# Motherboard_simple.net
KiCad netlist of a schematic drawn in EAGLE
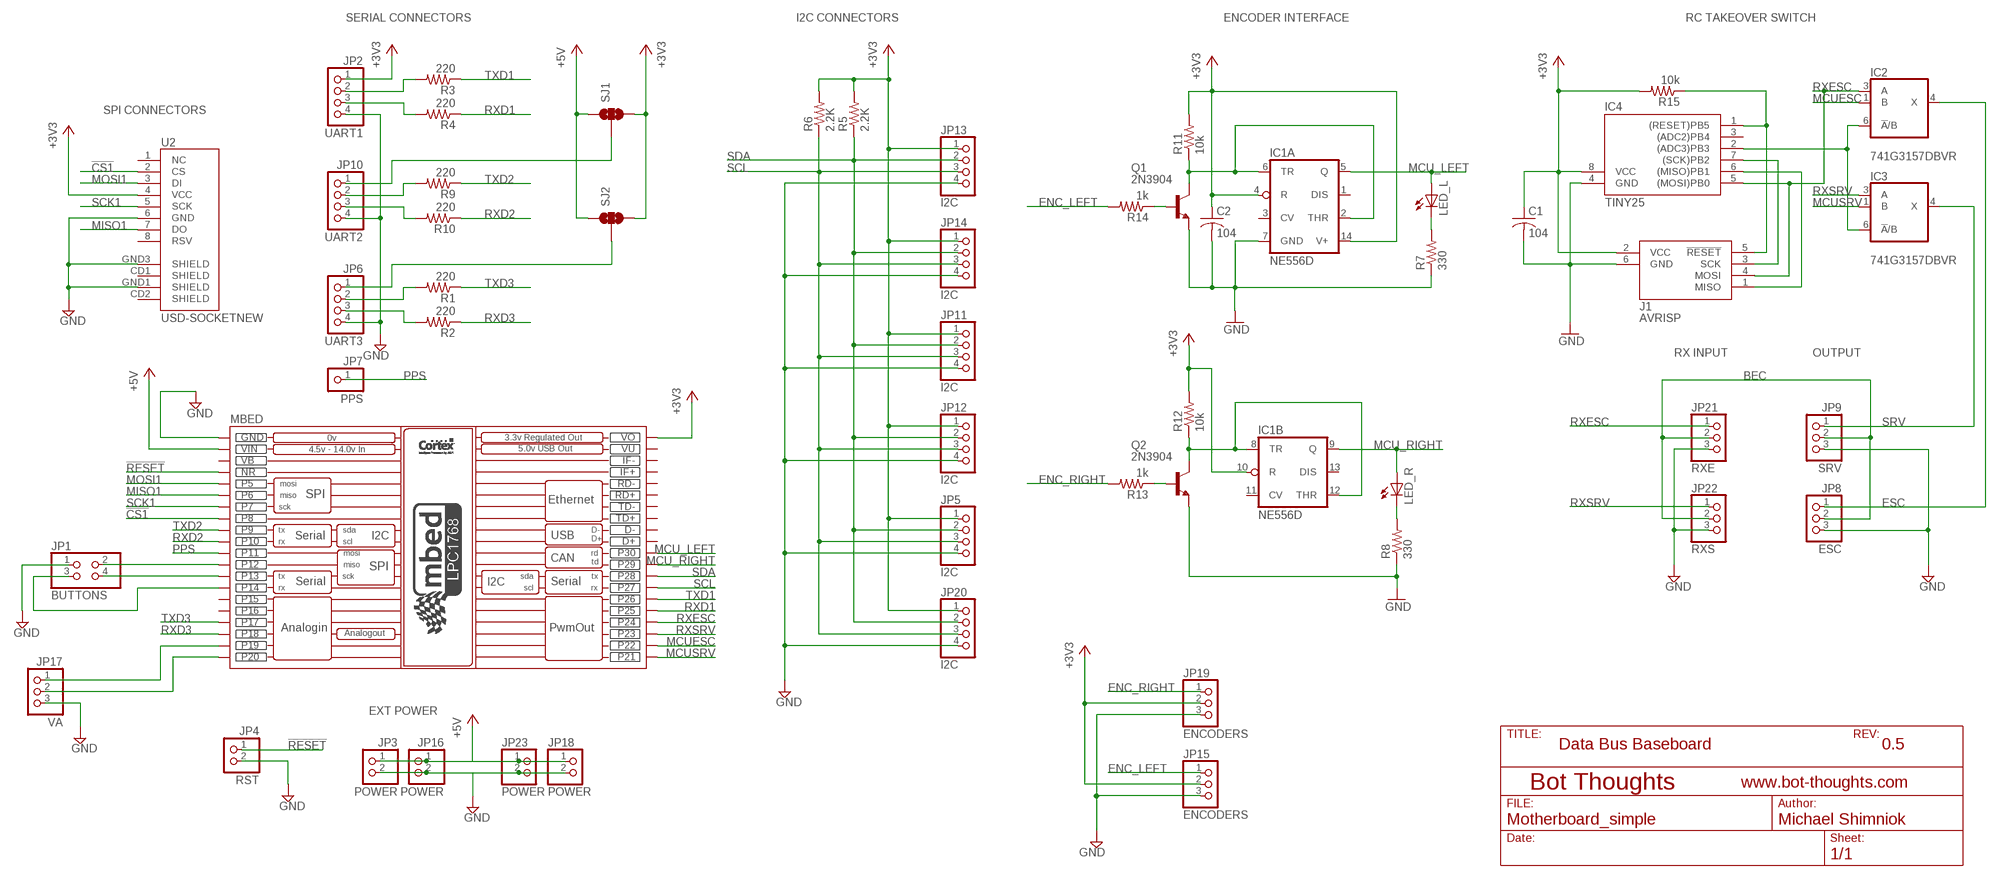
[diagram p0: schematic, sheet 1]

(export (version "E")
  (design (tool "Eeschema 10.0.6"))
  (components
    (comp (ref "C1")
      (value "104")
      (footprint "eagle-import:C050-025X075")
      (libsource (lib "eagle-import") (part "C-US050-025X075"))
    )
    (comp (ref "C2")
      (value "104")
      (footprint "eagle-import:C050-025X075")
      (libsource (lib "eagle-import") (part "C-US050-025X075"))
    )
    (comp (ref "IC1")
      (value "NE556D")
      (footprint "eagle-import:SO14")
      (libsource (lib "eagle-import") (part "556DNE"))
    )
    (comp (ref "IC2")
      (value "741G3157DBVR")
      (footprint "eagle-import:DBV_R-PDSO-G6")
      (libsource (lib "eagle-import") (part "741G3157DBVR"))
    )
    (comp (ref "IC3")
      (value "741G3157DBVR")
      (footprint "eagle-import:DBV_R-PDSO-G6")
      (libsource (lib "eagle-import") (part "741G3157DBVR"))
    )
    (comp (ref "IC4")
      (value "TINY25")
      (footprint "eagle-import:DIL08")
      (libsource (lib "eagle-import") (part "TINY138P3"))
    )
    (comp (ref "J1")
      (value "AVRISP")
      (footprint "eagle-import:CON6P2R")
      (libsource (lib "eagle-import") (part "AVRISP6"))
    )
    (comp (ref "JP1")
      (value "BUTTONS")
      (footprint "eagle-import:2X02")
      (libsource (lib "eagle-import") (part "PINHD-2X02_2.54"))
    )
    (comp (ref "JP2")
      (value "UART1")
      (footprint "eagle-import:1X04-S")
      (libsource (lib "eagle-import") (part "PINHD-1X04_2.54-S"))
    )
    (comp (ref "JP3")
      (value "POWER")
      (footprint "eagle-import:1X02-S")
      (libsource (lib "eagle-import") (part "PINHD-1X02_2.54-S"))
    )
    (comp (ref "JP4")
      (value "RST")
      (footprint "eagle-import:1X02-S")
      (libsource (lib "eagle-import") (part "PINHD-1X02_2.54-S"))
    )
    (comp (ref "JP5")
      (value "I2C")
      (footprint "eagle-import:1X04-S")
      (libsource (lib "eagle-import") (part "PINHD-1X04_2.54-S"))
    )
    (comp (ref "JP6")
      (value "UART3")
      (footprint "eagle-import:1X04-S")
      (libsource (lib "eagle-import") (part "PINHD-1X04_2.54-S"))
    )
    (comp (ref "JP7")
      (value "PPS")
      (footprint "eagle-import:1X01-S")
      (libsource (lib "eagle-import") (part "PINHD-1X01_2.54-S"))
    )
    (comp (ref "JP8")
      (value "ESC")
      (footprint "eagle-import:1X03-S")
      (libsource (lib "eagle-import") (part "PINHD-1X03_2.54-S"))
    )
    (comp (ref "JP9")
      (value "SRV")
      (footprint "eagle-import:1X03-S")
      (libsource (lib "eagle-import") (part "PINHD-1X03_2.54-S"))
    )
    (comp (ref "JP10")
      (value "UART2")
      (footprint "eagle-import:1X04-S")
      (libsource (lib "eagle-import") (part "PINHD-1X04_2.54-S"))
    )
    (comp (ref "JP11")
      (value "I2C")
      (footprint "eagle-import:1X04-S")
      (libsource (lib "eagle-import") (part "PINHD-1X04_2.54-S"))
    )
    (comp (ref "JP12")
      (value "I2C")
      (footprint "eagle-import:1X04-S")
      (libsource (lib "eagle-import") (part "PINHD-1X04_2.54-S"))
    )
    (comp (ref "JP13")
      (value "I2C")
      (footprint "eagle-import:1X04-S")
      (libsource (lib "eagle-import") (part "PINHD-1X04_2.54-S"))
    )
    (comp (ref "JP14")
      (value "I2C")
      (footprint "eagle-import:1X04-S")
      (libsource (lib "eagle-import") (part "PINHD-1X04_2.54-S"))
    )
    (comp (ref "JP15")
      (value "ENCODERS")
      (footprint "eagle-import:1X03-S")
      (libsource (lib "eagle-import") (part "PINHD-1X03_2.54-S"))
    )
    (comp (ref "JP16")
      (value "POWER")
      (footprint "eagle-import:1X02-S")
      (libsource (lib "eagle-import") (part "PINHD-1X02_2.54-S"))
    )
    (comp (ref "JP17")
      (value "VA")
      (footprint "eagle-import:1X03-S")
      (libsource (lib "eagle-import") (part "PINHD-1X03_2.54-S"))
    )
    (comp (ref "JP18")
      (value "POWER")
      (footprint "eagle-import:1X02-S")
      (libsource (lib "eagle-import") (part "PINHD-1X02_2.54-S"))
    )
    (comp (ref "JP19")
      (value "ENCODERS")
      (footprint "eagle-import:1X03-S")
      (libsource (lib "eagle-import") (part "PINHD-1X03_2.54-S"))
    )
    (comp (ref "JP20")
      (value "I2C")
      (footprint "eagle-import:1X04-S")
      (libsource (lib "eagle-import") (part "PINHD-1X04_2.54-S"))
    )
    (comp (ref "JP21")
      (value "RXE")
      (footprint "eagle-import:1X03-S")
      (libsource (lib "eagle-import") (part "PINHD-1X03_2.54-S"))
    )
    (comp (ref "JP22")
      (value "RXS")
      (footprint "eagle-import:1X03-S")
      (libsource (lib "eagle-import") (part "PINHD-1X03_2.54-S"))
    )
    (comp (ref "JP23")
      (value "POWER")
      (footprint "eagle-import:1X02-S")
      (libsource (lib "eagle-import") (part "PINHD-1X02_2.54-S"))
    )
    (comp (ref "LED_L")
      (value "LED3MM")
      (footprint "eagle-import:LED3MM")
      (libsource (lib "eagle-import") (part "LED3MM"))
    )
    (comp (ref "LED_R")
      (value "LED3MM")
      (footprint "eagle-import:LED3MM")
      (libsource (lib "eagle-import") (part "LED3MM"))
    )
    (comp (ref "MBED")
      (value "MBED_NXP_LPC1768")
      (footprint "eagle-import:MBED-KIT")
      (fields (field (name "MPN") "2212S-20SG-85"))
      (libsource (lib "eagle-import") (part "MBED_NXP_LPC1768"))
    )
    (comp (ref "Q1")
      (value "2N3904")
      (footprint "eagle-import:TO92")
      (libsource (lib "eagle-import") (part "2N3904"))
    )
    (comp (ref "Q2")
      (value "2N3904")
      (footprint "eagle-import:TO92")
      (libsource (lib "eagle-import") (part "2N3904"))
    )
    (comp (ref "R1")
      (value "220")
      (footprint "eagle-import:0204_5")
      (fields (field (name "MPN") "WCR0805-220RFI"))
      (libsource (lib "eagle-import") (part "R-US_0204/5"))
    )
    (comp (ref "R2")
      (value "220")
      (footprint "eagle-import:0204_5")
      (fields (field (name "MPN") "WCR0805-220RFI"))
      (libsource (lib "eagle-import") (part "R-US_0204/5"))
    )
    (comp (ref "R3")
      (value "220")
      (footprint "eagle-import:0204_5")
      (fields (field (name "MPN") "WCR0805-220RFI"))
      (libsource (lib "eagle-import") (part "R-US_0204/5"))
    )
    (comp (ref "R4")
      (value "220")
      (footprint "eagle-import:0204_5")
      (fields (field (name "MPN") "WCR0805-220RFI"))
      (libsource (lib "eagle-import") (part "R-US_0204/5"))
    )
    (comp (ref "R5")
      (value "2.2K")
      (footprint "eagle-import:0204_5")
      (libsource (lib "eagle-import") (part "R-US_0204/5"))
    )
    (comp (ref "R6")
      (value "2.2K")
      (footprint "eagle-import:0204_5")
      (libsource (lib "eagle-import") (part "R-US_0204/5"))
    )
    (comp (ref "R7")
      (value "330")
      (footprint "eagle-import:0204_5")
      (libsource (lib "eagle-import") (part "R-US_0204/5"))
    )
    (comp (ref "R8")
      (value "330")
      (footprint "eagle-import:0204_5")
      (libsource (lib "eagle-import") (part "R-US_0204/5"))
    )
    (comp (ref "R9")
      (value "220")
      (footprint "eagle-import:0204_5")
      (fields (field (name "MPN") "WCR0805-220RFI"))
      (libsource (lib "eagle-import") (part "R-US_0204/5"))
    )
    (comp (ref "R10")
      (value "220")
      (footprint "eagle-import:0204_5")
      (fields (field (name "MPN") "WCR0805-220RFI"))
      (libsource (lib "eagle-import") (part "R-US_0204/5"))
    )
    (comp (ref "R11")
      (value "10k")
      (footprint "eagle-import:0204_5")
      (libsource (lib "eagle-import") (part "R-US_0204/5"))
    )
    (comp (ref "R12")
      (value "10k")
      (footprint "eagle-import:0204_5")
      (libsource (lib "eagle-import") (part "R-US_0204/5"))
    )
    (comp (ref "R13")
      (value "1k")
      (footprint "eagle-import:0204_5")
      (libsource (lib "eagle-import") (part "R-US_0204/5"))
    )
    (comp (ref "R14")
      (value "1k")
      (footprint "eagle-import:0204_5")
      (libsource (lib "eagle-import") (part "R-US_0204/5"))
    )
    (comp (ref "R15")
      (value "10k")
      (footprint "eagle-import:0204_5")
      (libsource (lib "eagle-import") (part "R-US_0204/5"))
    )
    (comp (ref "SJ1")
      (value "SOLDERJUMPER_2WAYS")
      (footprint "eagle-import:SJ_3")
      (libsource (lib "eagle-import") (part "SOLDERJUMPER_2WAYS"))
    )
    (comp (ref "SJ2")
      (value "SOLDERJUMPER_2WAYS")
      (footprint "eagle-import:SJ_3")
      (libsource (lib "eagle-import") (part "SOLDERJUMPER_2WAYS"))
    )
    (comp (ref "U2")
      (value "USD-SOCKETNEW")
      (footprint "eagle-import:MICRO-SD-SOCKET-PP")
      (libsource (lib "eagle-import") (part "USD-SOCKETNEW"))
    )
  )
  (nets
    (net (code "1") (name "+3V3") (class "Default")
      (node (ref "C1") (pin "1") (pinfunction "1_1") (pintype "passive"))
      (node (ref "C2") (pin "1") (pinfunction "1_1") (pintype "passive"))
      (node (ref "IC1") (pin "10") (pinfunction "R_10") (pintype "input"))
      (node (ref "IC1") (pin "14") (pinfunction "V+_14") (pintype "power_in"))
      (node (ref "IC1") (pin "4") (pinfunction "R_4") (pintype "input"))
      (node (ref "IC4") (pin "8") (pinfunction "VCC_8") (pintype "power_in"))
      (node (ref "J1") (pin "2") (pinfunction "VCC_2") (pintype "power_in"))
      (node (ref "JP11") (pin "1") (pinfunction "1_1") (pintype "passive"))
      (node (ref "JP12") (pin "1") (pinfunction "1_1") (pintype "passive"))
      (node (ref "JP13") (pin "1") (pinfunction "1_1") (pintype "passive"))
      (node (ref "JP14") (pin "1") (pinfunction "1_1") (pintype "passive"))
      (node (ref "JP15") (pin "2") (pinfunction "2_2") (pintype "passive"))
      (node (ref "JP19") (pin "2") (pinfunction "2_2") (pintype "passive"))
      (node (ref "JP2") (pin "1") (pinfunction "1_1") (pintype "passive"))
      (node (ref "JP20") (pin "1") (pinfunction "1_1") (pintype "passive"))
      (node (ref "JP5") (pin "1") (pinfunction "1_1") (pintype "passive"))
      (node (ref "MBED") (pin "VOUT") (pinfunction "VO_VOUT") (pintype "power_in"))
      (node (ref "R11") (pin "2") (pinfunction "2_2") (pintype "passive"))
      (node (ref "R12") (pin "2") (pinfunction "2_2") (pintype "passive"))
      (node (ref "R15") (pin "2") (pinfunction "2_2") (pintype "passive"))
      (node (ref "R5") (pin "2") (pinfunction "2_2") (pintype "passive"))
      (node (ref "R6") (pin "2") (pinfunction "2_2") (pintype "passive"))
      (node (ref "SJ1") (pin "3") (pinfunction "3_3") (pintype "passive"))
      (node (ref "SJ2") (pin "3") (pinfunction "3_3") (pintype "passive"))
      (node (ref "U2") (pin "4") (pinfunction "VCC_4") (pintype "bidirectional"))
    )
    (net (code "2") (name "+5V") (class "Default")
      (node (ref "JP16") (pin "1") (pinfunction "1_1") (pintype "passive"))
      (node (ref "JP18") (pin "1") (pinfunction "1_1") (pintype "passive"))
      (node (ref "JP23") (pin "1") (pinfunction "1_1") (pintype "passive"))
      (node (ref "JP3") (pin "1") (pinfunction "1_1") (pintype "passive"))
      (node (ref "MBED") (pin "VIN") (pinfunction "VIN_VIN") (pintype "power_in"))
      (node (ref "SJ1") (pin "1") (pinfunction "1_1") (pintype "passive"))
      (node (ref "SJ2") (pin "1") (pinfunction "1_1") (pintype "passive"))
    )
    (net (code "3") (name "/BEC") (class "Default")
      (node (ref "JP21") (pin "2") (pinfunction "2_2") (pintype "passive"))
      (node (ref "JP22") (pin "2") (pinfunction "2_2") (pintype "passive"))
      (node (ref "JP8") (pin "2") (pinfunction "2_2") (pintype "passive"))
      (node (ref "JP9") (pin "2") (pinfunction "2_2") (pintype "passive"))
    )
    (net (code "4") (name "/ENC_LEFT") (class "Default")
      (node (ref "JP15") (pin "1") (pinfunction "1_1") (pintype "passive"))
      (node (ref "R14") (pin "2") (pinfunction "2_2") (pintype "passive"))
    )
    (net (code "5") (name "/ENC_RIGHT") (class "Default")
      (node (ref "JP19") (pin "1") (pinfunction "1_1") (pintype "passive"))
      (node (ref "R13") (pin "2") (pinfunction "2_2") (pintype "passive"))
    )
    (net (code "6") (name "/ESC") (class "Default")
      (node (ref "IC2") (pin "4") (pinfunction "X_4") (pintype "bidirectional"))
      (node (ref "JP8") (pin "1") (pinfunction "1_1") (pintype "passive"))
    )
    (net (code "7") (name "/MCUESC") (class "Default")
      (node (ref "IC2") (pin "1") (pinfunction "B_1") (pintype "bidirectional"))
      (node (ref "MBED") (pin "P$22") (pinfunction "P22_P$22") (pintype "bidirectional"))
    )
    (net (code "8") (name "/MCUSRV") (class "Default")
      (node (ref "IC3") (pin "1") (pinfunction "B_1") (pintype "bidirectional"))
      (node (ref "MBED") (pin "P$21") (pinfunction "P21_P$21") (pintype "bidirectional"))
    )
    (net (code "9") (name "/MCU_LEFT") (class "Default")
      (node (ref "IC1") (pin "5") (pinfunction "Q_5") (pintype "output"))
      (node (ref "LED_L") (pin "A") (pinfunction "A_A") (pintype "passive"))
      (node (ref "MBED") (pin "P$30") (pinfunction "P30_P$30") (pintype "bidirectional"))
    )
    (net (code "10") (name "/MCU_RIGHT") (class "Default")
      (node (ref "IC1") (pin "9") (pinfunction "Q_9") (pintype "output"))
      (node (ref "LED_R") (pin "A") (pinfunction "A_A") (pintype "passive"))
      (node (ref "MBED") (pin "P$29") (pinfunction "P29_P$29") (pintype "bidirectional"))
    )
    (net (code "11") (name "/MISO1") (class "Default")
      (node (ref "MBED") (pin "P$6") (pinfunction "P6_P$6") (pintype "bidirectional"))
      (node (ref "U2") (pin "7") (pinfunction "DO_7") (pintype "bidirectional"))
    )
    (net (code "12") (name "/MOSI1") (class "Default")
      (node (ref "MBED") (pin "P$5") (pinfunction "P5_P$5") (pintype "bidirectional"))
      (node (ref "U2") (pin "3") (pinfunction "DI_3") (pintype "bidirectional"))
    )
    (net (code "13") (name "/PPS") (class "Default")
      (node (ref "JP7") (pin "1") (pinfunction "1_1") (pintype "passive"))
      (node (ref "MBED") (pin "P$11") (pinfunction "P11_P$11") (pintype "bidirectional"))
    )
    (net (code "14") (name "/RXD1") (class "Default")
      (node (ref "MBED") (pin "P$25") (pinfunction "P25_P$25") (pintype "bidirectional"))
      (node (ref "R4") (pin "1") (pinfunction "1_1") (pintype "passive"))
    )
    (net (code "15") (name "/RXD2") (class "Default")
      (node (ref "MBED") (pin "P$10") (pinfunction "P10_P$10") (pintype "bidirectional"))
      (node (ref "R10") (pin "1") (pinfunction "1_1") (pintype "passive"))
    )
    (net (code "16") (name "/RXD3") (class "Default")
      (node (ref "MBED") (pin "P$18") (pinfunction "P18_P$18") (pintype "bidirectional"))
      (node (ref "R2") (pin "1") (pinfunction "1_1") (pintype "passive"))
    )
    (net (code "17") (name "/RXESC") (class "Default")
      (node (ref "IC2") (pin "3") (pinfunction "A_3") (pintype "bidirectional"))
      (node (ref "IC4") (pin "5") (pinfunction "(MOSI)PB0_5") (pintype "bidirectional"))
      (node (ref "J1") (pin "4") (pinfunction "MOSI_4") (pintype "output"))
      (node (ref "JP21") (pin "1") (pinfunction "1_1") (pintype "passive"))
      (node (ref "MBED") (pin "P$24") (pinfunction "P24_P$24") (pintype "bidirectional"))
    )
    (net (code "18") (name "/RXSRV") (class "Default")
      (node (ref "IC3") (pin "3") (pinfunction "A_3") (pintype "bidirectional"))
      (node (ref "JP22") (pin "1") (pinfunction "1_1") (pintype "passive"))
      (node (ref "MBED") (pin "P$23") (pinfunction "P23_P$23") (pintype "bidirectional"))
    )
    (net (code "19") (name "/SCK1") (class "Default")
      (node (ref "MBED") (pin "P$7") (pinfunction "P7_P$7") (pintype "bidirectional"))
      (node (ref "U2") (pin "5") (pinfunction "SCK_5") (pintype "bidirectional"))
    )
    (net (code "20") (name "/SCL") (class "Default")
      (node (ref "JP11") (pin "3") (pinfunction "3_3") (pintype "passive"))
      (node (ref "JP12") (pin "3") (pinfunction "3_3") (pintype "passive"))
      (node (ref "JP13") (pin "3") (pinfunction "3_3") (pintype "passive"))
      (node (ref "JP14") (pin "3") (pinfunction "3_3") (pintype "passive"))
      (node (ref "JP20") (pin "3") (pinfunction "3_3") (pintype "passive"))
      (node (ref "JP5") (pin "3") (pinfunction "3_3") (pintype "passive"))
      (node (ref "MBED") (pin "P$27") (pinfunction "P27_P$27") (pintype "bidirectional"))
      (node (ref "R6") (pin "1") (pinfunction "1_1") (pintype "passive"))
    )
    (net (code "21") (name "/SDA") (class "Default")
      (node (ref "JP11") (pin "2") (pinfunction "2_2") (pintype "passive"))
      (node (ref "JP12") (pin "2") (pinfunction "2_2") (pintype "passive"))
      (node (ref "JP13") (pin "2") (pinfunction "2_2") (pintype "passive"))
      (node (ref "JP14") (pin "2") (pinfunction "2_2") (pintype "passive"))
      (node (ref "JP20") (pin "2") (pinfunction "2_2") (pintype "passive"))
      (node (ref "JP5") (pin "2") (pinfunction "2_2") (pintype "passive"))
      (node (ref "MBED") (pin "P$28") (pinfunction "P28_P$28") (pintype "bidirectional"))
      (node (ref "R5") (pin "1") (pinfunction "1_1") (pintype "passive"))
    )
    (net (code "22") (name "/SRV") (class "Default")
      (node (ref "IC3") (pin "4") (pinfunction "X_4") (pintype "bidirectional"))
      (node (ref "JP9") (pin "1") (pinfunction "1_1") (pintype "passive"))
    )
    (net (code "23") (name "/TXD1") (class "Default")
      (node (ref "MBED") (pin "P$26") (pinfunction "P26_P$26") (pintype "bidirectional"))
      (node (ref "R3") (pin "1") (pinfunction "1_1") (pintype "passive"))
    )
    (net (code "24") (name "/TXD2") (class "Default")
      (node (ref "MBED") (pin "P$9") (pinfunction "P9_P$9") (pintype "bidirectional"))
      (node (ref "R9") (pin "1") (pinfunction "1_1") (pintype "passive"))
    )
    (net (code "25") (name "/TXD3") (class "Default")
      (node (ref "MBED") (pin "P$17") (pinfunction "P17_P$17") (pintype "bidirectional"))
      (node (ref "R1") (pin "1") (pinfunction "1_1") (pintype "passive"))
    )
    (net (code "26") (name "/VB") (class "Default")
      (node (ref "MBED") (pin "VB") (pinfunction "VB_VB") (pintype "power_in"))
    )
    (net (code "27") (name "/VU") (class "Default")
      (node (ref "MBED") (pin "VU") (pinfunction "VU_VU") (pintype "power_in"))
    )
    (net (code "28") (name "/~{CS1}") (class "Default")
      (node (ref "MBED") (pin "P$8") (pinfunction "P8_P$8") (pintype "bidirectional"))
      (node (ref "U2") (pin "2") (pinfunction "CS_2") (pintype "bidirectional"))
    )
    (net (code "29") (name "/~{RESET}") (class "Default")
      (node (ref "JP4") (pin "1") (pinfunction "1_1") (pintype "passive"))
      (node (ref "MBED") (pin "NR") (pinfunction "NR_NR") (pintype "power_in"))
    )
    (net (code "30") (name "GND") (class "Default")
      (node (ref "C1") (pin "2") (pinfunction "2_2") (pintype "passive"))
      (node (ref "C2") (pin "2") (pinfunction "2_2") (pintype "passive"))
      (node (ref "IC1") (pin "7") (pinfunction "GND_7") (pintype "power_in"))
      (node (ref "IC4") (pin "4") (pinfunction "GND_4") (pintype "power_in"))
      (node (ref "J1") (pin "6") (pinfunction "GND_6") (pintype "power_in"))
      (node (ref "JP1") (pin "1") (pinfunction "1_1") (pintype "passive"))
      (node (ref "JP10") (pin "4") (pinfunction "4_4") (pintype "passive"))
      (node (ref "JP11") (pin "4") (pinfunction "4_4") (pintype "passive"))
      (node (ref "JP12") (pin "4") (pinfunction "4_4") (pintype "passive"))
      (node (ref "JP13") (pin "4") (pinfunction "4_4") (pintype "passive"))
      (node (ref "JP14") (pin "4") (pinfunction "4_4") (pintype "passive"))
      (node (ref "JP15") (pin "3") (pinfunction "3_3") (pintype "passive"))
      (node (ref "JP16") (pin "2") (pinfunction "2_2") (pintype "passive"))
      (node (ref "JP17") (pin "3") (pinfunction "3_3") (pintype "passive"))
      (node (ref "JP18") (pin "2") (pinfunction "2_2") (pintype "passive"))
      (node (ref "JP19") (pin "3") (pinfunction "3_3") (pintype "passive"))
      (node (ref "JP2") (pin "4") (pinfunction "4_4") (pintype "passive"))
      (node (ref "JP20") (pin "4") (pinfunction "4_4") (pintype "passive"))
      (node (ref "JP21") (pin "3") (pinfunction "3_3") (pintype "passive"))
      (node (ref "JP22") (pin "3") (pinfunction "3_3") (pintype "passive"))
      (node (ref "JP23") (pin "2") (pinfunction "2_2") (pintype "passive"))
      (node (ref "JP3") (pin "2") (pinfunction "2_2") (pintype "passive"))
      (node (ref "JP4") (pin "2") (pinfunction "2_2") (pintype "passive"))
      (node (ref "JP5") (pin "4") (pinfunction "4_4") (pintype "passive"))
      (node (ref "JP6") (pin "4") (pinfunction "4_4") (pintype "passive"))
      (node (ref "JP8") (pin "3") (pinfunction "3_3") (pintype "passive"))
      (node (ref "JP9") (pin "3") (pinfunction "3_3") (pintype "passive"))
      (node (ref "MBED") (pin "GND") (pinfunction "GND_GND") (pintype "power_in"))
      (node (ref "Q1") (pin "3") (pinfunction "E_3") (pintype "passive"))
      (node (ref "Q2") (pin "3") (pinfunction "E_3") (pintype "passive"))
      (node (ref "R7") (pin "1") (pinfunction "1_1") (pintype "passive"))
      (node (ref "R8") (pin "1") (pinfunction "1_1") (pintype "passive"))
      (node (ref "U2") (pin "6") (pinfunction "GND_6") (pintype "bidirectional"))
      (node (ref "U2") (pin "GND1") (pinfunction "SHIELD_GND1") (pintype "bidirectional"))
      (node (ref "U2") (pin "GND3") (pinfunction "SHIELD_GND3") (pintype "bidirectional"))
    )
    (net (code "31") (name "Net-(IC1A-THR)") (class "Default")
      (node (ref "IC1") (pin "2") (pinfunction "THR_2") (pintype "input"))
      (node (ref "IC1") (pin "6") (pinfunction "TR_6") (pintype "input"))
      (node (ref "Q1") (pin "1") (pinfunction "C_1") (pintype "passive"))
      (node (ref "R11") (pin "1") (pinfunction "1_1") (pintype "passive"))
    )
    (net (code "32") (name "Net-(IC1B-THR)") (class "Default")
      (node (ref "IC1") (pin "12") (pinfunction "THR_12") (pintype "input"))
      (node (ref "IC1") (pin "8") (pinfunction "TR_8") (pintype "input"))
      (node (ref "Q2") (pin "1") (pinfunction "C_1") (pintype "passive"))
      (node (ref "R12") (pin "1") (pinfunction "1_1") (pintype "passive"))
    )
    (net (code "33") (name "Net-(IC2A-~{A}{slash}B)") (class "Default")
      (node (ref "IC2") (pin "6") (pinfunction "~{A}/B_6") (pintype "input"))
      (node (ref "IC3") (pin "6") (pinfunction "~{A}/B_6") (pintype "input"))
      (node (ref "IC4") (pin "2") (pinfunction "(ADC3)PB3_2") (pintype "bidirectional"))
    )
    (net (code "34") (name "Net-(IC4-(MISO)PB1)") (class "Default")
      (node (ref "IC4") (pin "6") (pinfunction "(MISO)PB1_6") (pintype "bidirectional"))
      (node (ref "J1") (pin "1") (pinfunction "MISO_1") (pintype "input"))
    )
    (net (code "35") (name "Net-(IC4-(RESET)PB5)") (class "Default")
      (node (ref "IC4") (pin "1") (pinfunction "(RESET)PB5_1") (pintype "bidirectional"))
      (node (ref "J1") (pin "5") (pinfunction "~{RESET}_5") (pintype "output"))
      (node (ref "R15") (pin "1") (pinfunction "1_1") (pintype "passive"))
    )
    (net (code "36") (name "Net-(IC4-(SCK)PB2)") (class "Default")
      (node (ref "IC4") (pin "7") (pinfunction "(SCK)PB2_7") (pintype "bidirectional"))
      (node (ref "J1") (pin "3") (pinfunction "SCK_3") (pintype "output"))
    )
    (net (code "37") (name "Net-(JP2-Pad2)") (class "Default")
      (node (ref "JP2") (pin "2") (pinfunction "2_2") (pintype "passive"))
      (node (ref "R3") (pin "2") (pinfunction "2_2") (pintype "passive"))
    )
    (net (code "38") (name "Net-(JP2-Pad3)") (class "Default")
      (node (ref "JP2") (pin "3") (pinfunction "3_3") (pintype "passive"))
      (node (ref "R4") (pin "2") (pinfunction "2_2") (pintype "passive"))
    )
    (net (code "39") (name "Net-(JP6-Pad1)") (class "Default")
      (node (ref "JP6") (pin "1") (pinfunction "1_1") (pintype "passive"))
      (node (ref "SJ2") (pin "2") (pinfunction "2_2") (pintype "passive"))
    )
    (net (code "40") (name "Net-(JP6-Pad2)") (class "Default")
      (node (ref "JP6") (pin "2") (pinfunction "2_2") (pintype "passive"))
      (node (ref "R1") (pin "2") (pinfunction "2_2") (pintype "passive"))
    )
    (net (code "41") (name "Net-(JP6-Pad3)") (class "Default")
      (node (ref "JP6") (pin "3") (pinfunction "3_3") (pintype "passive"))
      (node (ref "R2") (pin "2") (pinfunction "2_2") (pintype "passive"))
    )
    (net (code "42") (name "Net-(JP10-Pad1)") (class "Default")
      (node (ref "JP10") (pin "1") (pinfunction "1_1") (pintype "passive"))
      (node (ref "SJ1") (pin "2") (pinfunction "2_2") (pintype "passive"))
    )
    (net (code "43") (name "Net-(JP10-Pad2)") (class "Default")
      (node (ref "JP10") (pin "2") (pinfunction "2_2") (pintype "passive"))
      (node (ref "R9") (pin "2") (pinfunction "2_2") (pintype "passive"))
    )
    (net (code "44") (name "Net-(JP10-Pad3)") (class "Default")
      (node (ref "JP10") (pin "3") (pinfunction "3_3") (pintype "passive"))
      (node (ref "R10") (pin "2") (pinfunction "2_2") (pintype "passive"))
    )
    (net (code "45") (name "Net-(LED_L-C)") (class "Default")
      (node (ref "LED_L") (pin "K") (pinfunction "C_K") (pintype "passive"))
      (node (ref "R7") (pin "2") (pinfunction "2_2") (pintype "passive"))
    )
    (net (code "46") (name "Net-(LED_R-C)") (class "Default")
      (node (ref "LED_R") (pin "K") (pinfunction "C_K") (pintype "passive"))
      (node (ref "R8") (pin "2") (pinfunction "2_2") (pintype "passive"))
    )
    (net (code "47") (name "Net-(MBED-P12)") (class "Default")
      (node (ref "JP1") (pin "2") (pinfunction "2_2") (pintype "passive"))
      (node (ref "MBED") (pin "P$12") (pinfunction "P12_P$12") (pintype "bidirectional"))
    )
    (net (code "48") (name "Net-(MBED-P13)") (class "Default")
      (node (ref "JP1") (pin "4") (pinfunction "4_4") (pintype "passive"))
      (node (ref "MBED") (pin "P$13") (pinfunction "P13_P$13") (pintype "bidirectional"))
    )
    (net (code "49") (name "Net-(MBED-P14)") (class "Default")
      (node (ref "JP1") (pin "3") (pinfunction "3_3") (pintype "passive"))
      (node (ref "MBED") (pin "P$14") (pinfunction "P14_P$14") (pintype "bidirectional"))
    )
    (net (code "50") (name "Net-(MBED-P19)") (class "Default")
      (node (ref "JP17") (pin "1") (pinfunction "1_1") (pintype "passive"))
      (node (ref "MBED") (pin "P$19") (pinfunction "P19_P$19") (pintype "bidirectional"))
    )
    (net (code "51") (name "Net-(MBED-P20)") (class "Default")
      (node (ref "JP17") (pin "2") (pinfunction "2_2") (pintype "passive"))
      (node (ref "MBED") (pin "P$20") (pinfunction "P20_P$20") (pintype "bidirectional"))
    )
    (net (code "52") (name "Net-(Q1-B)") (class "Default")
      (node (ref "Q1") (pin "2") (pinfunction "B_2") (pintype "passive"))
      (node (ref "R14") (pin "1") (pinfunction "1_1") (pintype "passive"))
    )
    (net (code "53") (name "Net-(Q2-B)") (class "Default")
      (node (ref "Q2") (pin "2") (pinfunction "B_2") (pintype "passive"))
      (node (ref "R13") (pin "1") (pinfunction "1_1") (pintype "passive"))
    )
    (net (code "54") (name "unconnected-(IC1A-CV-Pad3)") (class "Default")
      (node (ref "IC1") (pin "3") (pinfunction "CV_3") (pintype "input"))
    )
    (net (code "55") (name "unconnected-(IC1A-DIS-Pad1)") (class "Default")
      (node (ref "IC1") (pin "1") (pinfunction "DIS_1") (pintype "input"))
    )
    (net (code "56") (name "unconnected-(IC1B-CV-Pad11)") (class "Default")
      (node (ref "IC1") (pin "11") (pinfunction "CV_11") (pintype "input"))
    )
    (net (code "57") (name "unconnected-(IC1B-DIS-Pad13)") (class "Default")
      (node (ref "IC1") (pin "13") (pinfunction "DIS_13") (pintype "input"))
    )
    (net (code "58") (name "unconnected-(IC4-(ADC2)PB4-Pad3)") (class "Default")
      (node (ref "IC4") (pin "3") (pinfunction "(ADC2)PB4_3") (pintype "bidirectional"))
    )
    (net (code "59") (name "unconnected-(MBED-P15-PadP$15)") (class "Default")
      (node (ref "MBED") (pin "P$15") (pinfunction "P15_P$15") (pintype "bidirectional"))
    )
    (net (code "60") (name "unconnected-(MBED-P16-PadP$16)") (class "Default")
      (node (ref "MBED") (pin "P$16") (pinfunction "P16_P$16") (pintype "bidirectional"))
    )
    (net (code "61") (name "unconnected-(MBED-PadD+)") (class "Default")
      (node (ref "MBED") (pin "D+") (pinfunction "D+_D+") (pintype "bidirectional"))
    )
    (net (code "62") (name "unconnected-(MBED-PadD-)") (class "Default")
      (node (ref "MBED") (pin "D-") (pinfunction "D-_D-") (pintype "bidirectional"))
    )
    (net (code "63") (name "unconnected-(MBED-PadIF+)") (class "Default")
      (node (ref "MBED") (pin "IF+") (pinfunction "IF+_IF+") (pintype "bidirectional"))
    )
    (net (code "64") (name "unconnected-(MBED-PadIF-)") (class "Default")
      (node (ref "MBED") (pin "IF-") (pinfunction "IF-_IF-") (pintype "bidirectional"))
    )
    (net (code "65") (name "unconnected-(MBED-PadRD+)") (class "Default")
      (node (ref "MBED") (pin "RD+") (pinfunction "RD+_RD+") (pintype "bidirectional"))
    )
    (net (code "66") (name "unconnected-(MBED-PadRD-)") (class "Default")
      (node (ref "MBED") (pin "RD-") (pinfunction "RD-_RD-") (pintype "bidirectional"))
    )
    (net (code "67") (name "unconnected-(MBED-PadTD+)") (class "Default")
      (node (ref "MBED") (pin "TD+") (pinfunction "TD+_TD+") (pintype "bidirectional"))
    )
    (net (code "68") (name "unconnected-(MBED-PadTD-)") (class "Default")
      (node (ref "MBED") (pin "TD-") (pinfunction "TD-_TD-") (pintype "bidirectional"))
    )
    (net (code "69") (name "unconnected-(U2-NC-Pad1)") (class "Default")
      (node (ref "U2") (pin "1") (pinfunction "NC_1") (pintype "bidirectional"))
    )
    (net (code "70") (name "unconnected-(U2-RSV-Pad8)") (class "Default")
      (node (ref "U2") (pin "8") (pinfunction "RSV_8") (pintype "bidirectional"))
    )
    (net (code "71") (name "unconnected-(U2-SHIELD-PadCD1)") (class "Default")
      (node (ref "U2") (pin "CD1") (pinfunction "SHIELD_CD1") (pintype "bidirectional"))
    )
    (net (code "72") (name "unconnected-(U2-SHIELD-PadCD2)") (class "Default")
      (node (ref "U2") (pin "CD2") (pinfunction "SHIELD_CD2") (pintype "bidirectional"))
    )
  )
)
